# MIDI_Merge_Module_v0_2.net
KiCad netlist of a schematic drawn in EAGLE
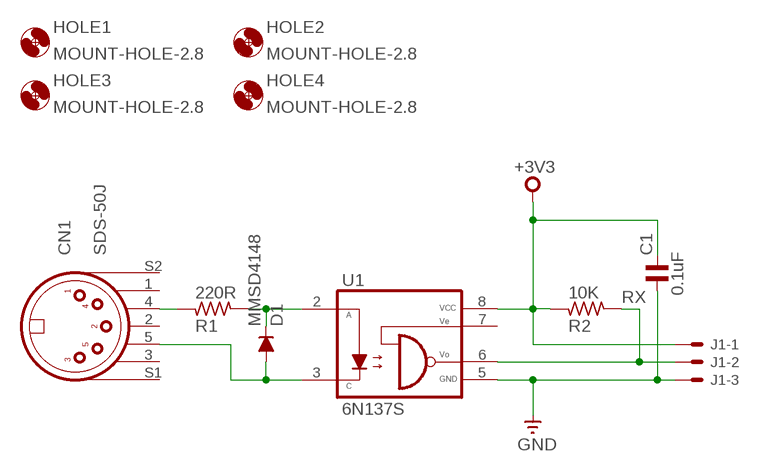
[diagram p0: schematic, sheet 1]

(export (version "E")
  (design (tool "Eeschema 10.0.6"))
  (components
    (comp (ref "C1")
      (value "0.1uF")
      (footprint "eagle-import:C1206MP")
      (libsource (lib "eagle-import") (part "C_1206MP"))
    )
    (comp (ref "CN1")
      (value "SDS-50J")
      (footprint "eagle-import:SDS-50J")
      (libsource (lib "eagle-import") (part "SDS-50J"))
    )
    (comp (ref "D1")
      (value "MMSD4148")
      (footprint "eagle-import:SOD123")
      (libsource (lib "eagle-import") (part "MMSD4148"))
    )
    (comp (ref "HOLE1")
      (value "MOUNT-HOLE-2.8")
      (footprint "eagle-import:2,8")
      (libsource (lib "eagle-import") (part "MOUNT-HOLE-2.8"))
    )
    (comp (ref "HOLE2")
      (value "MOUNT-HOLE-2.8")
      (footprint "eagle-import:2,8")
      (libsource (lib "eagle-import") (part "MOUNT-HOLE-2.8"))
    )
    (comp (ref "HOLE3")
      (value "MOUNT-HOLE-2.8")
      (footprint "eagle-import:2,8")
      (libsource (lib "eagle-import") (part "MOUNT-HOLE-2.8"))
    )
    (comp (ref "HOLE4")
      (value "MOUNT-HOLE-2.8")
      (footprint "eagle-import:2,8")
      (libsource (lib "eagle-import") (part "MOUNT-HOLE-2.8"))
    )
    (comp (ref "J1")
      (value "22-05-7038-03")
      (footprint "eagle-import:7395-03")
      (libsource (lib "eagle-import") (part "22-?-0305-7038"))
    )
    (comp (ref "R1")
      (value "220R")
      (footprint "eagle-import:R0805MP")
      (libsource (lib "eagle-import") (part "R_0805MP"))
    )
    (comp (ref "R2")
      (value "10K")
      (footprint "eagle-import:R0805MP")
      (libsource (lib "eagle-import") (part "R_0805MP"))
    )
    (comp (ref "U1")
      (value "6N137S")
      (footprint "eagle-import:SMD8")
      (libsource (lib "eagle-import") (part "6N137S"))
    )
  )
  (nets
    (net (code "1") (name "+3V3") (class "Default")
      (node (ref "C1") (pin "2") (pinfunction "2_2") (pintype "passive"))
      (node (ref "J1") (pin "1") (pinfunction "S_1") (pintype "passive"))
      (node (ref "R2") (pin "1") (pinfunction "1_1") (pintype "passive"))
      (node (ref "U1") (pin "8") (pinfunction "VCC_8") (pintype "passive"))
    )
    (net (code "2") (name "/RX") (class "Default")
      (node (ref "J1") (pin "2") (pinfunction "S_2") (pintype "passive"))
      (node (ref "R2") (pin "2") (pinfunction "2_2") (pintype "passive"))
      (node (ref "U1") (pin "6") (pinfunction "VO_6") (pintype "passive"))
    )
    (net (code "3") (name "GND") (class "Default")
      (node (ref "C1") (pin "1") (pinfunction "1_1") (pintype "passive"))
      (node (ref "J1") (pin "3") (pinfunction "S_3") (pintype "passive"))
      (node (ref "U1") (pin "5") (pinfunction "GND_5") (pintype "passive"))
    )
    (net (code "4") (name "Net-(CN1-Pad4)") (class "Default")
      (node (ref "CN1") (pin "4") (pinfunction "4_4") (pintype "passive"))
      (node (ref "R1") (pin "1") (pinfunction "1_1") (pintype "passive"))
    )
    (net (code "5") (name "Net-(U1-A)") (class "Default")
      (node (ref "D1") (pin "C") (pinfunction "C_C") (pintype "passive"))
      (node (ref "R1") (pin "2") (pinfunction "2_2") (pintype "passive"))
      (node (ref "U1") (pin "2") (pinfunction "A_2") (pintype "passive"))
    )
    (net (code "6") (name "Net-(U1-C)") (class "Default")
      (node (ref "CN1") (pin "5") (pinfunction "5_5") (pintype "passive"))
      (node (ref "D1") (pin "A") (pinfunction "A_A") (pintype "passive"))
      (node (ref "U1") (pin "3") (pinfunction "C_3") (pintype "passive"))
    )
    (net (code "7") (name "unconnected-(CN1-Pad1)") (class "Default")
      (node (ref "CN1") (pin "1") (pinfunction "1_1") (pintype "passive"))
    )
    (net (code "8") (name "unconnected-(CN1-Pad2)") (class "Default")
      (node (ref "CN1") (pin "2") (pinfunction "2_2") (pintype "passive"))
    )
    (net (code "9") (name "unconnected-(CN1-Pad3)") (class "Default")
      (node (ref "CN1") (pin "3") (pinfunction "3_3") (pintype "passive"))
    )
    (net (code "10") (name "unconnected-(CN1-PadS1)") (class "Default")
      (node (ref "CN1") (pin "S1") (pinfunction "S1_S1") (pintype "passive"))
    )
    (net (code "11") (name "unconnected-(CN1-PadS2)") (class "Default")
      (node (ref "CN1") (pin "S2") (pinfunction "S2_S2") (pintype "passive"))
    )
    (net (code "12") (name "unconnected-(U1-VE-Pad7)") (class "Default")
      (node (ref "U1") (pin "7") (pinfunction "VE_7") (pintype "passive"))
    )
  )
)
